# SRAM_WRP.net
KiCad netlist of a schematic drawn in Altium Designer
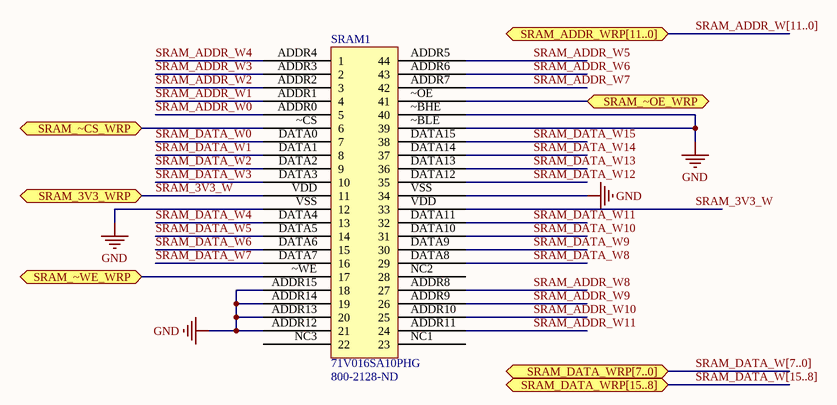
[diagram p0: SRAM_WRP.SchDoc]

(export (version "E")
  (design (tool "Eeschema 10.0.6"))
  (components
    (comp (ref "SRAM1")
      (value "71V016SA10PHG")
      (footprint "SRAM_TSSOP44-II")
      (description "IC SRAM 1MBIT 10NS 44TSOP")
      (fields
        (field (name "MANUFACTURER") "IDT, Integrated Device Technology Inc")
        (field (name "SUPPLIER PART NUMBER 1") "800-2128-ND")
      )
      (libsource (lib "DUTBoard") (part "71V016SA10PHG"))
    )
  )
  (nets
    (net (code "1") (name "/SRAM_3V3_W") (class "Default")
      (node (ref "SRAM1") (pin "VDD") (pinfunction "11_VDD") (pintype "passive"))
    )
    (net (code "2") (name "/SRAM_ADDR_W0") (class "Default")
      (node (ref "SRAM1") (pin "ADDR0") (pinfunction "5_ADDR0") (pintype "passive"))
    )
    (net (code "3") (name "/SRAM_ADDR_W1") (class "Default")
      (node (ref "SRAM1") (pin "ADDR1") (pinfunction "4_ADDR1") (pintype "passive"))
    )
    (net (code "4") (name "/SRAM_ADDR_W2") (class "Default")
      (node (ref "SRAM1") (pin "ADDR2") (pinfunction "3_ADDR2") (pintype "passive"))
    )
    (net (code "5") (name "/SRAM_ADDR_W3") (class "Default")
      (node (ref "SRAM1") (pin "ADDR3") (pinfunction "2_ADDR3") (pintype "passive"))
    )
    (net (code "6") (name "/SRAM_ADDR_W4") (class "Default")
      (node (ref "SRAM1") (pin "ADDR4") (pinfunction "1_ADDR4") (pintype "passive"))
    )
    (net (code "7") (name "/SRAM_ADDR_W5") (class "Default")
      (node (ref "SRAM1") (pin "ADDR5") (pinfunction "44_ADDR5") (pintype "passive"))
    )
    (net (code "8") (name "/SRAM_ADDR_W6") (class "Default")
      (node (ref "SRAM1") (pin "ADDR6") (pinfunction "43_ADDR6") (pintype "passive"))
    )
    (net (code "9") (name "/SRAM_ADDR_W7") (class "Default")
      (node (ref "SRAM1") (pin "ADDR7") (pinfunction "42_ADDR7") (pintype "passive"))
    )
    (net (code "10") (name "/SRAM_ADDR_W8") (class "Default")
      (node (ref "SRAM1") (pin "ADDR8") (pinfunction "27_ADDR8") (pintype "passive"))
    )
    (net (code "11") (name "/SRAM_ADDR_W9") (class "Default")
      (node (ref "SRAM1") (pin "ADDR9") (pinfunction "26_ADDR9") (pintype "passive"))
    )
    (net (code "12") (name "/SRAM_ADDR_W10") (class "Default")
      (node (ref "SRAM1") (pin "ADDR10") (pinfunction "25_ADDR10") (pintype "passive"))
    )
    (net (code "13") (name "/SRAM_ADDR_W11") (class "Default")
      (node (ref "SRAM1") (pin "ADDR11") (pinfunction "24_ADDR11") (pintype "passive"))
    )
    (net (code "15") (name "/SRAM_DATA_W0") (class "Default")
      (node (ref "SRAM1") (pin "DATA0") (pinfunction "7_DATA0") (pintype "passive"))
    )
    (net (code "16") (name "/SRAM_DATA_W1") (class "Default")
      (node (ref "SRAM1") (pin "DATA1") (pinfunction "8_DATA1") (pintype "passive"))
    )
    (net (code "17") (name "/SRAM_DATA_W2") (class "Default")
      (node (ref "SRAM1") (pin "DATA2") (pinfunction "9_DATA2") (pintype "passive"))
    )
    (net (code "18") (name "/SRAM_DATA_W3") (class "Default")
      (node (ref "SRAM1") (pin "DATA3") (pinfunction "10_DATA3") (pintype "passive"))
    )
    (net (code "19") (name "/SRAM_DATA_W4") (class "Default")
      (node (ref "SRAM1") (pin "DATA4") (pinfunction "13_DATA4") (pintype "passive"))
    )
    (net (code "20") (name "/SRAM_DATA_W5") (class "Default")
      (node (ref "SRAM1") (pin "DATA5") (pinfunction "14_DATA5") (pintype "passive"))
    )
    (net (code "21") (name "/SRAM_DATA_W6") (class "Default")
      (node (ref "SRAM1") (pin "DATA6") (pinfunction "15_DATA6") (pintype "passive"))
    )
    (net (code "22") (name "/SRAM_DATA_W7") (class "Default")
      (node (ref "SRAM1") (pin "DATA7") (pinfunction "16_DATA7") (pintype "passive"))
    )
    (net (code "23") (name "/SRAM_DATA_W8") (class "Default")
      (node (ref "SRAM1") (pin "DATA8") (pinfunction "29_DATA8") (pintype "passive"))
    )
    (net (code "24") (name "/SRAM_DATA_W9") (class "Default")
      (node (ref "SRAM1") (pin "DATA9") (pinfunction "30_DATA9") (pintype "passive"))
    )
    (net (code "25") (name "/SRAM_DATA_W10") (class "Default")
      (node (ref "SRAM1") (pin "DATA10") (pinfunction "31_DATA10") (pintype "passive"))
    )
    (net (code "26") (name "/SRAM_DATA_W11") (class "Default")
      (node (ref "SRAM1") (pin "DATA11") (pinfunction "32_DATA11") (pintype "passive"))
    )
    (net (code "27") (name "/SRAM_DATA_W12") (class "Default")
      (node (ref "SRAM1") (pin "DATA12") (pinfunction "35_DATA12") (pintype "passive"))
    )
    (net (code "28") (name "/SRAM_DATA_W13") (class "Default")
      (node (ref "SRAM1") (pin "DATA13") (pinfunction "36_DATA13") (pintype "passive"))
    )
    (net (code "29") (name "/SRAM_DATA_W14") (class "Default")
      (node (ref "SRAM1") (pin "DATA14") (pinfunction "37_DATA14") (pintype "passive"))
    )
    (net (code "30") (name "/SRAM_DATA_W15") (class "Default")
      (node (ref "SRAM1") (pin "DATA15") (pinfunction "38_DATA15") (pintype "passive"))
    )
    (net (code "33") (name "/SRAM_~CS_WRP") (class "Default")
      (node (ref "SRAM1") (pin "~CS") (pinfunction "6_~CS") (pintype "passive"))
    )
    (net (code "34") (name "/SRAM_~OE_WRP") (class "Default")
      (node (ref "SRAM1") (pin "~OE") (pinfunction "41_~OE") (pintype "passive"))
    )
    (net (code "35") (name "/SRAM_~WE_WRP") (class "Default")
      (node (ref "SRAM1") (pin "~WE") (pinfunction "17_~WE") (pintype "passive"))
    )
    (net (code "36") (name "GND") (class "Default")
      (node (ref "SRAM1") (pin "ADDR12") (pinfunction "21_ADDR12") (pintype "passive"))
      (node (ref "SRAM1") (pin "ADDR13") (pinfunction "20_ADDR13") (pintype "passive"))
      (node (ref "SRAM1") (pin "ADDR14") (pinfunction "19_ADDR14") (pintype "passive"))
      (node (ref "SRAM1") (pin "ADDR15") (pinfunction "18_ADDR15") (pintype "passive"))
      (node (ref "SRAM1") (pin "VSS") (pinfunction "12_VSS") (pintype "passive"))
      (node (ref "SRAM1") (pin "~BHE") (pinfunction "40_~BHE") (pintype "passive"))
      (node (ref "SRAM1") (pin "~BLE") (pinfunction "39_~BLE") (pintype "passive"))
    )
    (net (code "37") (name "unconnected-(SRAM1-22-PadNC3)") (class "Default")
      (node (ref "SRAM1") (pin "NC3") (pinfunction "22_NC3") (pintype "passive"))
    )
    (net (code "38") (name "unconnected-(SRAM1-23-PadNC1)") (class "Default")
      (node (ref "SRAM1") (pin "NC1") (pinfunction "23_NC1") (pintype "passive"))
    )
    (net (code "39") (name "unconnected-(SRAM1-28-PadNC2)") (class "Default")
      (node (ref "SRAM1") (pin "NC2") (pinfunction "28_NC2") (pintype "passive"))
    )
  )
)
